# Sheet1_ASC.net
KiCad netlist of a schematic drawn in Altium Designer
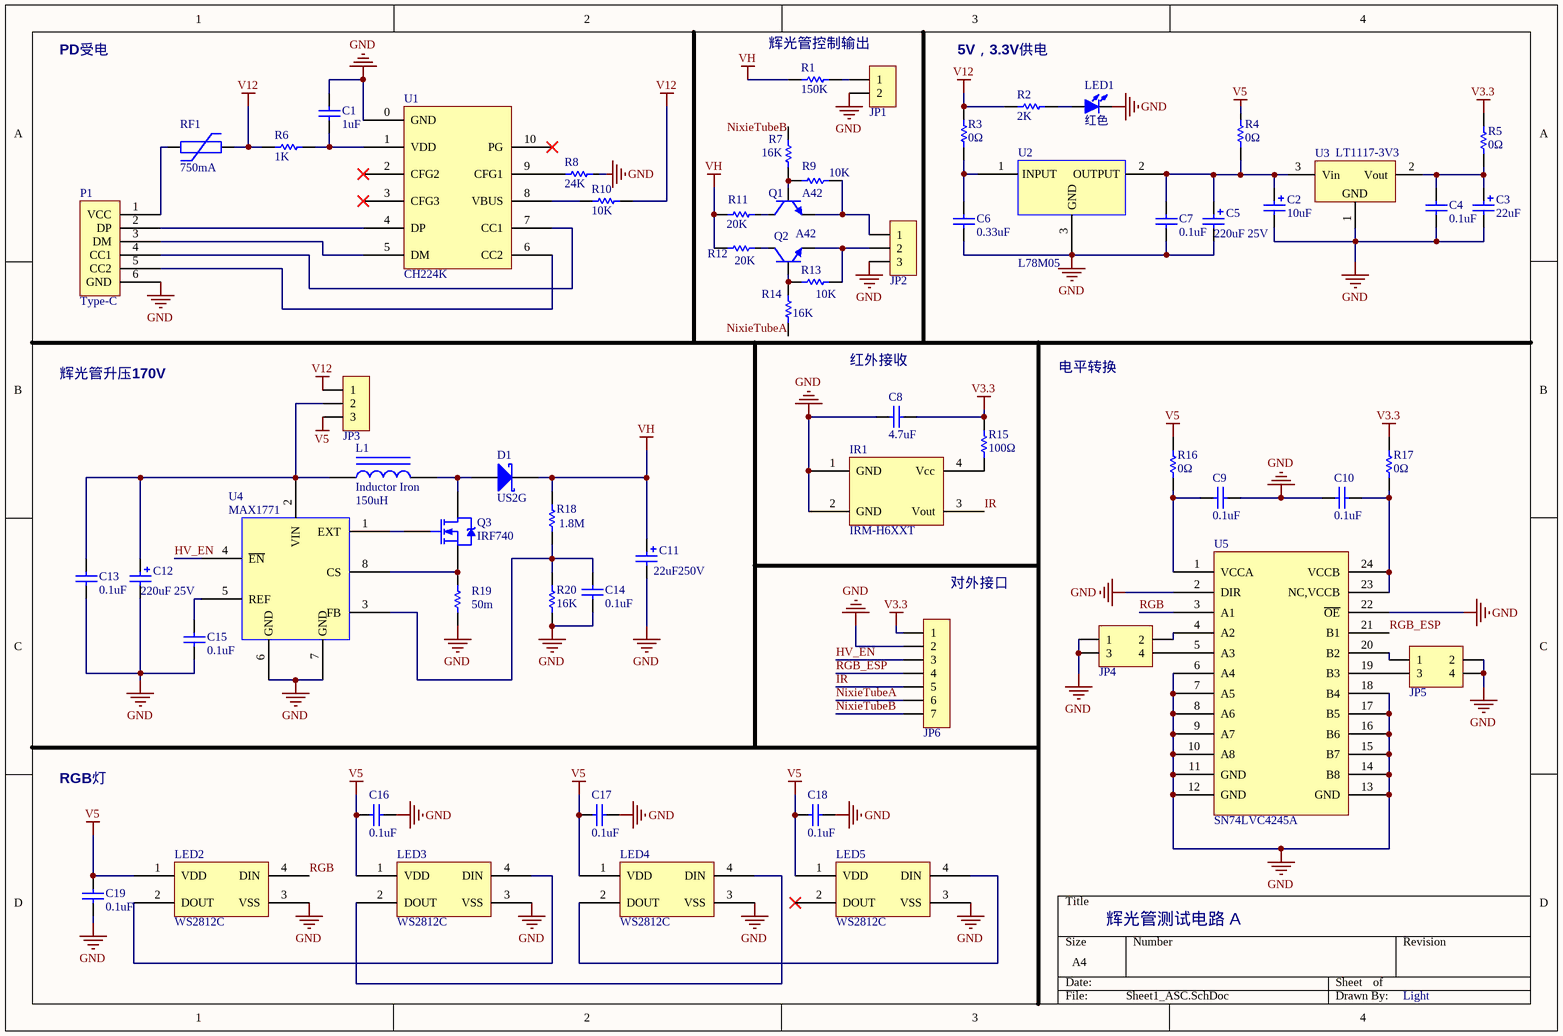
[diagram p0: Sheet1_ASC.SchDoc]

(export (version "E")
  (design (tool "Eeschema 10.0.6"))
  (components
    (comp (ref "C1")
      (value "1uF")
      (footprint "C 0805_L")
      (description "Capacitor")
      (fields (field (name "Comment") "Cap") (field (name "PUBLISHER") "Altium Limited"))
      (libsource (lib "Nixie") (part "Cap"))
    )
    (comp (ref "C2")
      (value "10uF")
      (footprint "CM B(4*5.4)")
      (description "Polarized Capacitor (Radial)")
      (fields (field (name "Comment") "Cap Pol1") (field (name "PUBLISHER") "Altium Limited"))
      (libsource (lib "Nixie") (part "Cap Pol1"))
    )
    (comp (ref "C3")
      (value "22uF")
      (footprint "CD C(6032)")
      (description "Polarized Capacitor (Radial)")
      (fields (field (name "Comment") "Cap Pol1") (field (name "PUBLISHER") "Altium Limited"))
      (libsource (lib "Nixie") (part "Cap Pol1"))
    )
    (comp (ref "C4")
      (value "0.1uF")
      (footprint "C 0805_L")
      (description "Capacitor")
      (fields (field (name "Comment") "Cap") (field (name "PUBLISHER") "Altium Limited"))
      (libsource (lib "Nixie") (part "Cap"))
    )
    (comp (ref "C5")
      (value "220uF 25V")
      (footprint "CM E(8*10.2)")
      (description "Polarized Capacitor (Radial)")
      (fields
        (field (name "VOLTAGE") "16V")
        (field (name "Comment") "Cap Pol1")
        (field (name "PUBLISHER") "Altium Limited")
      )
      (libsource (lib "Nixie") (part "Cap Pol1_2"))
    )
    (comp (ref "C6")
      (value "0.33uF")
      (footprint "C 0805_L")
      (description "Capacitor")
      (fields (field (name "Comment") "Cap") (field (name "PUBLISHER") "Altium Limited"))
      (libsource (lib "Nixie") (part "Cap"))
    )
    (comp (ref "C7")
      (value "0.1uF")
      (footprint "C 0805_L")
      (description "Capacitor")
      (fields (field (name "Comment") "Cap") (field (name "PUBLISHER") "Altium Limited"))
      (libsource (lib "Nixie") (part "Cap"))
    )
    (comp (ref "C8")
      (value "4.7uF")
      (footprint "C 0805_L")
      (description "Capacitor")
      (fields (field (name "Comment") "Cap") (field (name "PUBLISHER") "Altium Limited"))
      (libsource (lib "Nixie") (part "Cap"))
    )
    (comp (ref "C9")
      (value "0.1uF")
      (footprint "C 0805_L")
      (description "Capacitor")
      (fields (field (name "Comment") "Cap") (field (name "PUBLISHER") "Altium Limited"))
      (libsource (lib "Nixie") (part "Cap"))
    )
    (comp (ref "C10")
      (value "0.1uF")
      (footprint "C 0805_L")
      (description "Capacitor")
      (fields (field (name "Comment") "Cap") (field (name "PUBLISHER") "Altium Limited"))
      (libsource (lib "Nixie") (part "Cap"))
    )
    (comp (ref "C11")
      (value "22uF250V")
      (footprint "CAP 5.0*10*16-H - GD")
      (description "Polarized Capacitor (Radial)")
      (fields (field (name "Comment") "Cap Pol1") (field (name "PUBLISHER") "Altium Limited"))
      (libsource (lib "Nixie") (part "Cap Pol1_3"))
    )
    (comp (ref "C12")
      (value "220uF 25V")
      (footprint "CM E(8*10.2)")
      (description "Polarized Capacitor (Radial)")
      (fields
        (field (name "VOLTAGE") "16V")
        (field (name "Comment") "Cap Pol1")
        (field (name "PUBLISHER") "Altium Limited")
      )
      (libsource (lib "Nixie") (part "Cap Pol1_2"))
    )
    (comp (ref "C13")
      (value "0.1uF")
      (footprint "C 0805_L")
      (description "Capacitor")
      (fields (field (name "Comment") "Cap") (field (name "PUBLISHER") "Altium Limited"))
      (libsource (lib "Nixie") (part "Cap"))
    )
    (comp (ref "C14")
      (value "0.1uF")
      (footprint "C 0805_L")
      (description "Capacitor")
      (fields (field (name "Comment") "Cap") (field (name "PUBLISHER") "Altium Limited"))
      (libsource (lib "Nixie") (part "Cap"))
    )
    (comp (ref "C15")
      (value "0.1uF")
      (footprint "C 0805_L")
      (description "Capacitor")
      (fields (field (name "Comment") "Cap") (field (name "PUBLISHER") "Altium Limited"))
      (libsource (lib "Schlib1") (part "Cap"))
    )
    (comp (ref "C16")
      (value "0.1uF")
      (footprint "C 0805_L")
      (description "Capacitor")
      (fields (field (name "Comment") "Cap") (field (name "PUBLISHER") "Altium Limited"))
      (libsource (lib "Nixie") (part "Cap"))
    )
    (comp (ref "C17")
      (value "0.1uF")
      (footprint "C 0805_L")
      (description "Capacitor")
      (fields (field (name "Comment") "Cap") (field (name "PUBLISHER") "Altium Limited"))
      (libsource (lib "Nixie") (part "Cap"))
    )
    (comp (ref "C18")
      (value "0.1uF")
      (footprint "C 0805_L")
      (description "Capacitor")
      (fields (field (name "Comment") "Cap") (field (name "PUBLISHER") "Altium Limited"))
      (libsource (lib "Nixie") (part "Cap"))
    )
    (comp (ref "C19")
      (value "0.1uF")
      (footprint "C 0805_L")
      (description "Capacitor")
      (fields (field (name "Comment") "Cap") (field (name "PUBLISHER") "Altium Limited"))
      (libsource (lib "Nixie") (part "Cap"))
    )
    (comp (ref "D1")
      (value "US2G")
      (footprint "SMA")
      (description "Schottky Diode")
      (fields (field (name "PUBLISHER") "Altium Limited"))
      (libsource (lib "Nixie") (part "D Schottky"))
    )
    (comp (ref "IR1") (value "IRM-H6XXT") (footprint "SMD4_IR") (libsource (lib "Nixie") (part "IR")))
    (comp (ref "JP1")
      (value "HDR-1X2")
      (footprint "HDR2.54-LI-2P")
      (description "2P接插件")
      (fields (field (name "版权归属") "封装库来自淘宝 ID：黄晶宝石"))
      (libsource (lib "Nixie") (part "Header 2"))
    )
    (comp (ref "JP2")
      (value "HDR-1X3")
      (footprint "HDR2.54-LI-3P")
      (description "3P接插件")
      (fields (field (name "版权归属") "封装库来自淘宝 ID：黄晶宝石"))
      (libsource (lib "Nixie") (part "Header 3"))
    )
    (comp (ref "JP3")
      (value "HDR-1X3")
      (footprint "HDR2.54-LI-3P")
      (description "3P接插件")
      (fields (field (name "版权归属") "封装库来自淘宝 ID：黄晶宝石"))
      (libsource (lib "Nixie") (part "Header 3"))
    )
    (comp (ref "JP4")
      (value "Header2X2")
      (footprint "HDR2.54-LI-2x2P")
      (description "2*2P接插件")
      (fields (field (name "版权归属") "封装库来自淘宝 ID：黄晶宝石"))
      (libsource (lib "Nixie") (part "Header 2X2"))
    )
    (comp (ref "JP5")
      (value "Header2X2")
      (footprint "HDR2.54-LI-2x2P")
      (description "2*2P接插件")
      (fields (field (name "版权归属") "封装库来自淘宝 ID：黄晶宝石"))
      (libsource (lib "Nixie") (part "Header 2X2"))
    )
    (comp (ref "JP6")
      (value "HDR-1X7")
      (footprint "HDR2.54-LI-7P")
      (description "7P接插件")
      (fields (field (name "版权归属") "封装库来自淘宝 ID：黄晶宝石"))
      (libsource (lib "Nixie") (part "Header 7"))
    )
    (comp (ref "L1")
      (value "Inductor Iron")
      (footprint "CDRH127")
      (description "Magnetic-Core Inductor")
      (fields (field (name "ALTIUM_VALUE") "150uH") (field (name "PUBLISHER") "Altium Limited"))
      (libsource (lib "Nixie") (part "Inductor Iron"))
    )
    (comp (ref "LED1")
      (value "红色")
      (footprint "LED 1206R")
      (description "贴片LED")
      (fields (field (name "版权归属") "封装库来自淘宝 ID：黄晶宝石"))
      (libsource (lib "Nixie") (part "LED-SMD"))
    )
    (comp (ref "LED2")
      (value "WS2812C")
      (footprint "WS2812")
      (description "RGB发光管")
      (libsource (lib "Nixie") (part "WS2812"))
    )
    (comp (ref "LED3")
      (value "WS2812C")
      (footprint "WS2812")
      (description "RGB发光管")
      (libsource (lib "Nixie") (part "WS2812"))
    )
    (comp (ref "LED4")
      (value "WS2812C")
      (footprint "WS2812")
      (description "RGB发光管")
      (libsource (lib "Nixie") (part "WS2812"))
    )
    (comp (ref "LED5")
      (value "WS2812C")
      (footprint "WS2812")
      (description "RGB发光管")
      (libsource (lib "Nixie") (part "WS2812"))
    )
    (comp (ref "P1")
      (value "Type-C")
      (footprint "USB-C-SMD_10P-P1.00-L6.8-W8.9")
      (description "Type-C 接口")
      (libsource (lib "Nixie") (part "Type-C"))
    )
    (comp (ref "Q1")
      (value "A42")
      (footprint "SOT23-3L")
      (description "NPN三极管")
      (fields (field (name "PUBLISHER") "Altium Limited"))
      (libsource (lib "Nixie") (part "BCP68"))
    )
    (comp (ref "Q2")
      (value "A42")
      (footprint "SOT23-3L")
      (description "NPN三极管")
      (fields (field (name "PUBLISHER") "Altium Limited"))
      (libsource (lib "Nixie") (part "BCP68"))
    )
    (comp (ref "Q3")
      (value "IRF740")
      (footprint "TO-263-2L")
      (description "N-Channel Power MOSFET")
      (fields (field (name "PUBLISHER") "Altium Limited"))
      (libsource (lib "Nixie") (part "NMOS-2"))
    )
    (comp (ref "R1")
      (value "150K")
      (footprint "R 0805_L")
      (description "Semiconductor Resistor")
      (fields (field (name "Comment") "Res Semi") (field (name "PUBLISHER") "Altium Limited"))
      (libsource (lib "Schlib1") (part "Res"))
    )
    (comp (ref "R2")
      (value "2K")
      (footprint "R 0805_L")
      (description "Resistor")
      (fields (field (name "PUBLISHER") "Altium Limited"))
      (libsource (lib "Nixie") (part "Resistor"))
    )
    (comp (ref "R3")
      (value "0Ω")
      (footprint "R 0805_L")
      (description "Resistor")
      (fields (field (name "PUBLISHER") "Altium Limited"))
      (libsource (lib "Nixie") (part "Resistor"))
    )
    (comp (ref "R4")
      (value "0Ω")
      (footprint "R 0805_L")
      (description "Resistor")
      (fields (field (name "PUBLISHER") "Altium Limited"))
      (libsource (lib "Nixie") (part "Resistor"))
    )
    (comp (ref "R5")
      (value "0Ω")
      (footprint "R 0805_L")
      (description "Resistor")
      (fields (field (name "PUBLISHER") "Altium Limited"))
      (libsource (lib "Nixie") (part "Resistor"))
    )
    (comp (ref "R6")
      (value "1K")
      (footprint "R 1206_L")
      (description "Resistor")
      (fields (field (name "PUBLISHER") "Altium Limited"))
      (libsource (lib "Nixie") (part "Resistor"))
    )
    (comp (ref "R7")
      (value "16K")
      (footprint "R 0805_L")
      (description "Resistor")
      (fields (field (name "PUBLISHER") "Altium Limited"))
      (libsource (lib "Nixie") (part "Resistor"))
    )
    (comp (ref "R8")
      (value "24K")
      (footprint "R 0805_L")
      (description "Resistor")
      (fields (field (name "PUBLISHER") "Altium Limited"))
      (libsource (lib "Nixie") (part "Resistor"))
    )
    (comp (ref "R9")
      (value "10K")
      (footprint "R 0805_L")
      (description "Resistor")
      (fields (field (name "PUBLISHER") "Altium Limited"))
      (libsource (lib "Nixie") (part "Resistor"))
    )
    (comp (ref "R10")
      (value "10K")
      (footprint "R 0805_L")
      (description "Resistor")
      (fields (field (name "PUBLISHER") "Altium Limited"))
      (libsource (lib "Nixie") (part "Resistor"))
    )
    (comp (ref "R11")
      (value "20K")
      (footprint "R 0805_L")
      (description "Semiconductor Resistor")
      (fields (field (name "Comment") "Res Semi") (field (name "PUBLISHER") "Altium Limited"))
      (libsource (lib "Schlib1") (part "Res"))
    )
    (comp (ref "R12")
      (value "20K")
      (footprint "R 0805_L")
      (description "Semiconductor Resistor")
      (fields (field (name "Comment") "Res Semi") (field (name "PUBLISHER") "Altium Limited"))
      (libsource (lib "Schlib1") (part "Res"))
    )
    (comp (ref "R13")
      (value "10K")
      (footprint "R 0805_L")
      (description "Resistor")
      (fields (field (name "PUBLISHER") "Altium Limited"))
      (libsource (lib "Nixie") (part "Resistor"))
    )
    (comp (ref "R14")
      (value "16K")
      (footprint "R 0805_L")
      (description "Resistor")
      (fields (field (name "PUBLISHER") "Altium Limited"))
      (libsource (lib "Nixie") (part "Resistor"))
    )
    (comp (ref "R15")
      (value "100Ω")
      (footprint "R 0805_L")
      (description "Resistor")
      (fields (field (name "PUBLISHER") "Altium Limited"))
      (libsource (lib "Nixie") (part "Resistor"))
    )
    (comp (ref "R16")
      (value "0Ω")
      (footprint "R 0805_L")
      (description "Resistor")
      (fields (field (name "PUBLISHER") "Altium Limited"))
      (libsource (lib "Nixie") (part "Resistor"))
    )
    (comp (ref "R17")
      (value "0Ω")
      (footprint "R 0805_L")
      (description "Resistor")
      (fields (field (name "PUBLISHER") "Altium Limited"))
      (libsource (lib "Nixie") (part "Resistor"))
    )
    (comp (ref "R18")
      (value "1.8M")
      (footprint "R 0805_L")
      (description "Semiconductor Resistor")
      (fields (field (name "Comment") "Res Semi") (field (name "PUBLISHER") "Altium Limited"))
      (libsource (lib "Nixie") (part "Res Semi"))
    )
    (comp (ref "R19")
      (value "50m")
      (footprint "R 1206_L")
      (description "Semiconductor Resistor")
      (fields (field (name "Comment") "Res Semi") (field (name "PUBLISHER") "Altium Limited"))
      (libsource (lib "Nixie") (part "Res Semi"))
    )
    (comp (ref "R20")
      (value "16K")
      (footprint "R 0805_L")
      (description "Resistor")
      (fields (field (name "PUBLISHER") "Altium Limited"))
      (libsource (lib "Nixie") (part "Resistor"))
    )
    (comp (ref "RF1")
      (value "750mA")
      (footprint "FU 1812")
      (description "PPTC自恢复保险丝")
      (fields (field (name "版权归属") "封装库来自淘宝卖家 ID：黄晶宝石"))
      (libsource (lib "Nixie") (part "PPTC"))
    )
    (comp (ref "U1")
      (value "CH224K")
      (footprint "ESSOP10")
      (description "PD协议受电芯片")
      (libsource (lib "Nixie") (part "CH224K"))
    )
    (comp (ref "U2") (value "L78M05") (footprint "TO-252-2L") (libsource (lib "Nixie") (part "L78M05")))
    (comp (ref "U3")
      (value "LT1117-3V3")
      (footprint "SOT223_L")
      (description "三端稳压芯片")
      (fields (field (name "版权归属") "源创客"))
      (libsource (lib "Nixie") (part "AMS1117"))
    )
    (comp (ref "U4") (value "MAX1771") (footprint "SOIC8") (libsource (lib "Nixie") (part "MAX1771")))
    (comp (ref "U5")
      (value "SN74LVC4245A")
      (footprint "TSSOP24_L")
      (description "双向电平转换")
      (libsource (lib "Schlib1") (part "74LVC4245"))
    )
  )
  (nets
    (net (code "1") (name "/HV_EN") (class "Default")
      (node (ref "JP6") (pin "3") (pinfunction "3_3") (pintype "passive"))
      (node (ref "U4") (pin "4") (pinfunction "~{EN}_4") (pintype "passive"))
    )
    (net (code "2") (name "/IR") (class "Default")
      (node (ref "IR1") (pin "3") (pinfunction "Vout_3") (pintype "passive"))
      (node (ref "JP6") (pin "5") (pinfunction "5_5") (pintype "passive"))
    )
    (net (code "3") (name "/NixieTubeA") (class "Default")
      (node (ref "JP6") (pin "6") (pinfunction "6_6") (pintype "passive"))
      (node (ref "R14") (pin "2") (pinfunction "2_2") (pintype "passive"))
    )
    (net (code "4") (name "/NixieTubeB") (class "Default")
      (node (ref "JP6") (pin "7") (pinfunction "7_7") (pintype "passive"))
      (node (ref "R7") (pin "2") (pinfunction "2_2") (pintype "passive"))
    )
    (net (code "5") (name "/RGB") (class "Default")
      (node (ref "LED2") (pin "4") (pinfunction "DIN_4") (pintype "passive"))
      (node (ref "U5") (pin "3") (pinfunction "A1_3") (pintype "passive"))
    )
    (net (code "6") (name "/RGB_ESP") (class "Default")
      (node (ref "JP6") (pin "4") (pinfunction "4_4") (pintype "passive"))
      (node (ref "U5") (pin "21") (pinfunction "B1_21") (pintype "passive"))
    )
    (net (code "7") (name "GND") (class "Default")
      (node (ref "C1") (pin "2") (pinfunction "2_2") (pintype "passive"))
      (node (ref "C10") (pin "2") (pinfunction "2_2") (pintype "passive"))
      (node (ref "C11") (pin "2") (pinfunction "2_2") (pintype "passive"))
      (node (ref "C12") (pin "2") (pinfunction "2_2") (pintype "passive"))
      (node (ref "C13") (pin "1") (pinfunction "1_1") (pintype "passive"))
      (node (ref "C14") (pin "1") (pinfunction "1_1") (pintype "passive"))
      (node (ref "C15") (pin "2") (pinfunction "2_2") (pintype "passive"))
      (node (ref "C16") (pin "1") (pinfunction "1_1") (pintype "passive"))
      (node (ref "C17") (pin "1") (pinfunction "1_1") (pintype "passive"))
      (node (ref "C18") (pin "1") (pinfunction "1_1") (pintype "passive"))
      (node (ref "C19") (pin "1") (pinfunction "1_1") (pintype "passive"))
      (node (ref "C2") (pin "2") (pinfunction "2_2") (pintype "passive"))
      (node (ref "C3") (pin "2") (pinfunction "2_2") (pintype "passive"))
      (node (ref "C4") (pin "1") (pinfunction "1_1") (pintype "passive"))
      (node (ref "C5") (pin "2") (pinfunction "2_2") (pintype "passive"))
      (node (ref "C6") (pin "1") (pinfunction "1_1") (pintype "passive"))
      (node (ref "C7") (pin "1") (pinfunction "1_1") (pintype "passive"))
      (node (ref "C8") (pin "2") (pinfunction "2_2") (pintype "passive"))
      (node (ref "C9") (pin "1") (pinfunction "1_1") (pintype "passive"))
      (node (ref "IR1") (pin "1") (pinfunction "GND_1") (pintype "passive"))
      (node (ref "IR1") (pin "2") (pinfunction "GND_2") (pintype "passive"))
      (node (ref "JP1") (pin "2") (pinfunction "2_2") (pintype "passive"))
      (node (ref "JP2") (pin "3") (pinfunction "3_3") (pintype "passive"))
      (node (ref "JP4") (pin "1") (pinfunction "1_1") (pintype "passive"))
      (node (ref "JP4") (pin "3") (pinfunction "3_3") (pintype "passive"))
      (node (ref "JP5") (pin "2") (pinfunction "2_2") (pintype "passive"))
      (node (ref "JP5") (pin "4") (pinfunction "4_4") (pintype "passive"))
      (node (ref "JP6") (pin "2") (pinfunction "2_2") (pintype "passive"))
      (node (ref "LED1") (pin "2") (pinfunction "K_2") (pintype "passive"))
      (node (ref "LED2") (pin "3") (pinfunction "VSS_3") (pintype "passive"))
      (node (ref "LED3") (pin "3") (pinfunction "VSS_3") (pintype "passive"))
      (node (ref "LED4") (pin "3") (pinfunction "VSS_3") (pintype "passive"))
      (node (ref "LED5") (pin "3") (pinfunction "VSS_3") (pintype "passive"))
      (node (ref "P1") (pin "6") (pinfunction "GND_6") (pintype "passive"))
      (node (ref "R19") (pin "2") (pinfunction "2_2") (pintype "passive"))
      (node (ref "R20") (pin "1") (pinfunction "1_1") (pintype "passive"))
      (node (ref "R8") (pin "1") (pinfunction "1_1") (pintype "passive"))
      (node (ref "U1") (pin "0") (pinfunction "GND_0") (pintype "passive"))
      (node (ref "U2") (pin "3") (pinfunction "GND_3") (pintype "passive"))
      (node (ref "U3") (pin "1") (pinfunction "GND_1") (pintype "passive"))
      (node (ref "U4") (pin "6") (pinfunction "GND_6") (pintype "passive"))
      (node (ref "U4") (pin "7") (pinfunction "GND_7") (pintype "passive"))
      (node (ref "U5") (pin "10") (pinfunction "A8_10") (pintype "passive"))
      (node (ref "U5") (pin "11") (pinfunction "GND_11") (pintype "passive"))
      (node (ref "U5") (pin "12") (pinfunction "GND_12") (pintype "passive"))
      (node (ref "U5") (pin "13") (pinfunction "GND_13") (pintype "passive"))
      (node (ref "U5") (pin "14") (pinfunction "B8_14") (pintype "passive"))
      (node (ref "U5") (pin "15") (pinfunction "B7_15") (pintype "passive"))
      (node (ref "U5") (pin "16") (pinfunction "B6_16") (pintype "passive"))
      (node (ref "U5") (pin "17") (pinfunction "B5_17") (pintype "passive"))
      (node (ref "U5") (pin "18") (pinfunction "B4_18") (pintype "passive"))
      (node (ref "U5") (pin "2") (pinfunction "DIR_2") (pintype "passive"))
      (node (ref "U5") (pin "22") (pinfunction "~{OE}_22") (pintype "passive"))
      (node (ref "U5") (pin "6") (pinfunction "A4_6") (pintype "passive"))
      (node (ref "U5") (pin "7") (pinfunction "A5_7") (pintype "passive"))
      (node (ref "U5") (pin "8") (pinfunction "A6_8") (pintype "passive"))
      (node (ref "U5") (pin "9") (pinfunction "A7_9") (pintype "passive"))
    )
    (net (code "8") (name "Net-(D1-A)") (class "Default")
      (node (ref "D1") (pin "1") (pinfunction "A_1") (pintype "passive"))
      (node (ref "L1") (pin "2") (pinfunction "2_2") (pintype "passive"))
      (node (ref "Q3") (pin "2") (pinfunction "D_2") (pintype "passive"))
    )
    (net (code "9") (name "Net-(IR1-Vcc)") (class "Default")
      (node (ref "IR1") (pin "4") (pinfunction "Vcc_4") (pintype "passive"))
      (node (ref "R15") (pin "1") (pinfunction "1_1") (pintype "passive"))
    )
    (net (code "10") (name "Net-(JP1-Pad1)") (class "Default")
      (node (ref "JP1") (pin "1") (pinfunction "1_1") (pintype "passive"))
      (node (ref "R1") (pin "2") (pinfunction "2_2") (pintype "passive"))
    )
    (net (code "11") (name "Net-(LED1-A)") (class "Default")
      (node (ref "LED1") (pin "1") (pinfunction "A_1") (pintype "passive"))
      (node (ref "R2") (pin "1") (pinfunction "1_1") (pintype "passive"))
    )
    (net (code "12") (name "Net-(LED2-DOUT)") (class "Default")
      (node (ref "LED2") (pin "2") (pinfunction "DOUT_2") (pintype "passive"))
      (node (ref "LED3") (pin "4") (pinfunction "DIN_4") (pintype "passive"))
    )
    (net (code "13") (name "Net-(LED3-DOUT)") (class "Default")
      (node (ref "LED3") (pin "2") (pinfunction "DOUT_2") (pintype "passive"))
      (node (ref "LED4") (pin "4") (pinfunction "DIN_4") (pintype "passive"))
    )
    (net (code "14") (name "Net-(LED4-DOUT)") (class "Default")
      (node (ref "LED4") (pin "2") (pinfunction "DOUT_2") (pintype "passive"))
      (node (ref "LED5") (pin "4") (pinfunction "DIN_4") (pintype "passive"))
    )
    (net (code "15") (name "Net-(P1-CC1)") (class "Default")
      (node (ref "P1") (pin "4") (pinfunction "CC1_4") (pintype "passive"))
      (node (ref "U1") (pin "7") (pinfunction "CC1_7") (pintype "passive"))
    )
    (net (code "16") (name "Net-(P1-CC2)") (class "Default")
      (node (ref "P1") (pin "5") (pinfunction "CC2_5") (pintype "passive"))
      (node (ref "U1") (pin "6") (pinfunction "CC2_6") (pintype "passive"))
    )
    (net (code "17") (name "Net-(P1-DM)") (class "Default")
      (node (ref "P1") (pin "3") (pinfunction "DM_3") (pintype "passive"))
      (node (ref "U1") (pin "5") (pinfunction "DM_5") (pintype "passive"))
    )
    (net (code "18") (name "Net-(P1-DP)") (class "Default")
      (node (ref "P1") (pin "2") (pinfunction "DP_2") (pintype "passive"))
      (node (ref "U1") (pin "4") (pinfunction "DP_4") (pintype "passive"))
    )
    (net (code "19") (name "Net-(P1-VCC)") (class "Default")
      (node (ref "P1") (pin "1") (pinfunction "VCC_1") (pintype "passive"))
      (node (ref "RF1") (pin "1") (pinfunction "1_1") (pintype "passive"))
    )
    (net (code "20") (name "Net-(Q1-B)") (class "Default")
      (node (ref "Q1") (pin "1") (pinfunction "B_1") (pintype "passive"))
      (node (ref "R7") (pin "1") (pinfunction "1_1") (pintype "passive"))
      (node (ref "R9") (pin "1") (pinfunction "1_1") (pintype "passive"))
    )
    (net (code "21") (name "Net-(Q1-C)") (class "Default")
      (node (ref "Q1") (pin "3") (pinfunction "C_3") (pintype "passive"))
      (node (ref "R11") (pin "2") (pinfunction "2_2") (pintype "passive"))
    )
    (net (code "22") (name "Net-(Q1-E)") (class "Default")
      (node (ref "JP2") (pin "1") (pinfunction "1_1") (pintype "passive"))
      (node (ref "Q1") (pin "2") (pinfunction "E_2") (pintype "passive"))
      (node (ref "R9") (pin "2") (pinfunction "2_2") (pintype "passive"))
    )
    (net (code "23") (name "Net-(Q2-B)") (class "Default")
      (node (ref "Q2") (pin "1") (pinfunction "B_1") (pintype "passive"))
      (node (ref "R13") (pin "1") (pinfunction "1_1") (pintype "passive"))
      (node (ref "R14") (pin "1") (pinfunction "1_1") (pintype "passive"))
    )
    (net (code "24") (name "Net-(Q2-C)") (class "Default")
      (node (ref "Q2") (pin "3") (pinfunction "C_3") (pintype "passive"))
      (node (ref "R12") (pin "2") (pinfunction "2_2") (pintype "passive"))
    )
    (net (code "25") (name "Net-(Q2-E)") (class "Default")
      (node (ref "JP2") (pin "2") (pinfunction "2_2") (pintype "passive"))
      (node (ref "Q2") (pin "2") (pinfunction "E_2") (pintype "passive"))
      (node (ref "R13") (pin "2") (pinfunction "2_2") (pintype "passive"))
    )
    (net (code "26") (name "Net-(Q3-G)") (class "Default")
      (node (ref "Q3") (pin "1") (pinfunction "G_1") (pintype "passive"))
      (node (ref "U4") (pin "1") (pinfunction "EXT_1") (pintype "passive"))
    )
    (net (code "27") (name "Net-(Q3-S)") (class "Default")
      (node (ref "Q3") (pin "3") (pinfunction "S_3") (pintype "passive"))
      (node (ref "R19") (pin "1") (pinfunction "1_1") (pintype "passive"))
      (node (ref "U4") (pin "8") (pinfunction "CS_8") (pintype "passive"))
    )
    (net (code "28") (name "Net-(U1-CFG1)") (class "Default")
      (node (ref "R8") (pin "2") (pinfunction "2_2") (pintype "passive"))
      (node (ref "U1") (pin "9") (pinfunction "CFG1_9") (pintype "passive"))
    )
    (net (code "29") (name "Net-(U1-VBUS)") (class "Default")
      (node (ref "R10") (pin "2") (pinfunction "2_2") (pintype "passive"))
      (node (ref "U1") (pin "8") (pinfunction "VBUS_8") (pintype "passive"))
    )
    (net (code "30") (name "Net-(U1-VDD)") (class "Default")
      (node (ref "C1") (pin "1") (pinfunction "1_1") (pintype "passive"))
      (node (ref "R6") (pin "1") (pinfunction "1_1") (pintype "passive"))
      (node (ref "U1") (pin "1") (pinfunction "VDD_1") (pintype "passive"))
    )
    (net (code "31") (name "Net-(U2-INPUT)") (class "Default")
      (node (ref "C6") (pin "2") (pinfunction "2_2") (pintype "passive"))
      (node (ref "R3") (pin "1") (pinfunction "1_1") (pintype "passive"))
      (node (ref "U2") (pin "1") (pinfunction "INPUT_1") (pintype "passive"))
    )
    (net (code "32") (name "Net-(U2-OUTPUT)") (class "Default")
      (node (ref "C2") (pin "1") (pinfunction "1_1") (pintype "passive"))
      (node (ref "C5") (pin "1") (pinfunction "1_1") (pintype "passive"))
      (node (ref "C7") (pin "2") (pinfunction "2_2") (pintype "passive"))
      (node (ref "R4") (pin "1") (pinfunction "1_1") (pintype "passive"))
      (node (ref "U2") (pin "2") (pinfunction "OUTPUT_2") (pintype "passive"))
      (node (ref "U3") (pin "3") (pinfunction "Vin_3") (pintype "passive"))
    )
    (net (code "33") (name "Net-(U3-Vout)") (class "Default")
      (node (ref "C3") (pin "1") (pinfunction "1_1") (pintype "passive"))
      (node (ref "C4") (pin "2") (pinfunction "2_2") (pintype "passive"))
      (node (ref "R5") (pin "1") (pinfunction "1_1") (pintype "passive"))
      (node (ref "U3") (pin "2") (pinfunction "Vout_2") (pintype "passive"))
    )
    (net (code "34") (name "Net-(U4-FB)") (class "Default")
      (node (ref "C14") (pin "2") (pinfunction "2_2") (pintype "passive"))
      (node (ref "R18") (pin "2") (pinfunction "2_2") (pintype "passive"))
      (node (ref "R20") (pin "2") (pinfunction "2_2") (pintype "passive"))
      (node (ref "U4") (pin "3") (pinfunction "FB_3") (pintype "passive"))
    )
    (net (code "35") (name "Net-(U4-REF)") (class "Default")
      (node (ref "C15") (pin "1") (pinfunction "1_1") (pintype "passive"))
      (node (ref "U4") (pin "5") (pinfunction "REF_5") (pintype "passive"))
    )
    (net (code "36") (name "Net-(U4-VIN)") (class "Default")
      (node (ref "C12") (pin "1") (pinfunction "1_1") (pintype "passive"))
      (node (ref "C13") (pin "2") (pinfunction "2_2") (pintype "passive"))
      (node (ref "JP3") (pin "2") (pinfunction "2_2") (pintype "passive"))
      (node (ref "L1") (pin "1") (pinfunction "1_1") (pintype "passive"))
      (node (ref "U4") (pin "2") (pinfunction "VIN_2") (pintype "passive"))
    )
    (net (code "37") (name "Net-(U5-A2)") (class "Default")
      (node (ref "JP4") (pin "2") (pinfunction "2_2") (pintype "passive"))
      (node (ref "U5") (pin "4") (pinfunction "A2_4") (pintype "passive"))
    )
    (net (code "38") (name "Net-(U5-A3)") (class "Default")
      (node (ref "JP4") (pin "4") (pinfunction "4_4") (pintype "passive"))
      (node (ref "U5") (pin "5") (pinfunction "A3_5") (pintype "passive"))
    )
    (net (code "39") (name "Net-(U5-B2)") (class "Default")
      (node (ref "JP5") (pin "1") (pinfunction "1_1") (pintype "passive"))
      (node (ref "U5") (pin "20") (pinfunction "B2_20") (pintype "passive"))
    )
    (net (code "40") (name "Net-(U5-B3)") (class "Default")
      (node (ref "JP5") (pin "3") (pinfunction "3_3") (pintype "passive"))
      (node (ref "U5") (pin "19") (pinfunction "B3_19") (pintype "passive"))
    )
    (net (code "41") (name "Net-(U5-NC,VCCB)") (class "Default")
      (node (ref "C10") (pin "1") (pinfunction "1_1") (pintype "passive"))
      (node (ref "R17") (pin "1") (pinfunction "1_1") (pintype "passive"))
      (node (ref "U5") (pin "23") (pinfunction "NC,VCCB_23") (pintype "passive"))
      (node (ref "U5") (pin "24") (pinfunction "VCCB_24") (pintype "passive"))
    )
    (net (code "42") (name "Net-(U5-VCCA)") (class "Default")
      (node (ref "C9") (pin "2") (pinfunction "2_2") (pintype "passive"))
      (node (ref "R16") (pin "1") (pinfunction "1_1") (pintype "passive"))
      (node (ref "U5") (pin "1") (pinfunction "VCCA_1") (pintype "passive"))
    )
    (net (code "43") (name "V3.3") (class "Default")
      (node (ref "C8") (pin "1") (pinfunction "1_1") (pintype "passive"))
      (node (ref "JP6") (pin "1") (pinfunction "1_1") (pintype "passive"))
      (node (ref "R15") (pin "2") (pinfunction "2_2") (pintype "passive"))
      (node (ref "R17") (pin "2") (pinfunction "2_2") (pintype "passive"))
      (node (ref "R5") (pin "2") (pinfunction "2_2") (pintype "passive"))
    )
    (net (code "44") (name "V5") (class "Default")
      (node (ref "C16") (pin "2") (pinfunction "2_2") (pintype "passive"))
      (node (ref "C17") (pin "2") (pinfunction "2_2") (pintype "passive"))
      (node (ref "C18") (pin "2") (pinfunction "2_2") (pintype "passive"))
      (node (ref "C19") (pin "2") (pinfunction "2_2") (pintype "passive"))
      (node (ref "JP3") (pin "3") (pinfunction "3_3") (pintype "passive"))
      (node (ref "LED2") (pin "1") (pinfunction "VDD_1") (pintype "passive"))
      (node (ref "LED3") (pin "1") (pinfunction "VDD_1") (pintype "passive"))
      (node (ref "LED4") (pin "1") (pinfunction "VDD_1") (pintype "passive"))
      (node (ref "LED5") (pin "1") (pinfunction "VDD_1") (pintype "passive"))
      (node (ref "R16") (pin "2") (pinfunction "2_2") (pintype "passive"))
      (node (ref "R4") (pin "2") (pinfunction "2_2") (pintype "passive"))
    )
    (net (code "45") (name "V12") (class "Default")
      (node (ref "JP3") (pin "1") (pinfunction "1_1") (pintype "passive"))
      (node (ref "R10") (pin "1") (pinfunction "1_1") (pintype "passive"))
      (node (ref "R2") (pin "2") (pinfunction "2_2") (pintype "passive"))
      (node (ref "R3") (pin "2") (pinfunction "2_2") (pintype "passive"))
      (node (ref "R6") (pin "2") (pinfunction "2_2") (pintype "passive"))
      (node (ref "RF1") (pin "2") (pinfunction "2_2") (pintype "passive"))
    )
    (net (code "46") (name "VH") (class "Default")
      (node (ref "C11") (pin "1") (pinfunction "1_1") (pintype "passive"))
      (node (ref "D1") (pin "2") (pinfunction "K_2") (pintype "passive"))
      (node (ref "R1") (pin "1") (pinfunction "1_1") (pintype "passive"))
      (node (ref "R11") (pin "1") (pinfunction "1_1") (pintype "passive"))
      (node (ref "R12") (pin "1") (pinfunction "1_1") (pintype "passive"))
      (node (ref "R18") (pin "1") (pinfunction "1_1") (pintype "passive"))
    )
    (net (code "47") (name "unconnected-(LED5-DOUT-Pad2)") (class "Default")
      (node (ref "LED5") (pin "2") (pinfunction "DOUT_2") (pintype "passive+no_connect"))
    )
    (net (code "48") (name "unconnected-(U1-CFG2-Pad2)") (class "Default")
      (node (ref "U1") (pin "2") (pinfunction "CFG2_2") (pintype "passive+no_connect"))
    )
    (net (code "49") (name "unconnected-(U1-CFG3-Pad3)") (class "Default")
      (node (ref "U1") (pin "3") (pinfunction "CFG3_3") (pintype "passive+no_connect"))
    )
    (net (code "50") (name "unconnected-(U1-PG-Pad10)") (class "Default")
      (node (ref "U1") (pin "10") (pinfunction "PG_10") (pintype "passive+no_connect"))
    )
  )
)
